# PulseInOut.net
KiCad netlist of a schematic drawn in EAGLE
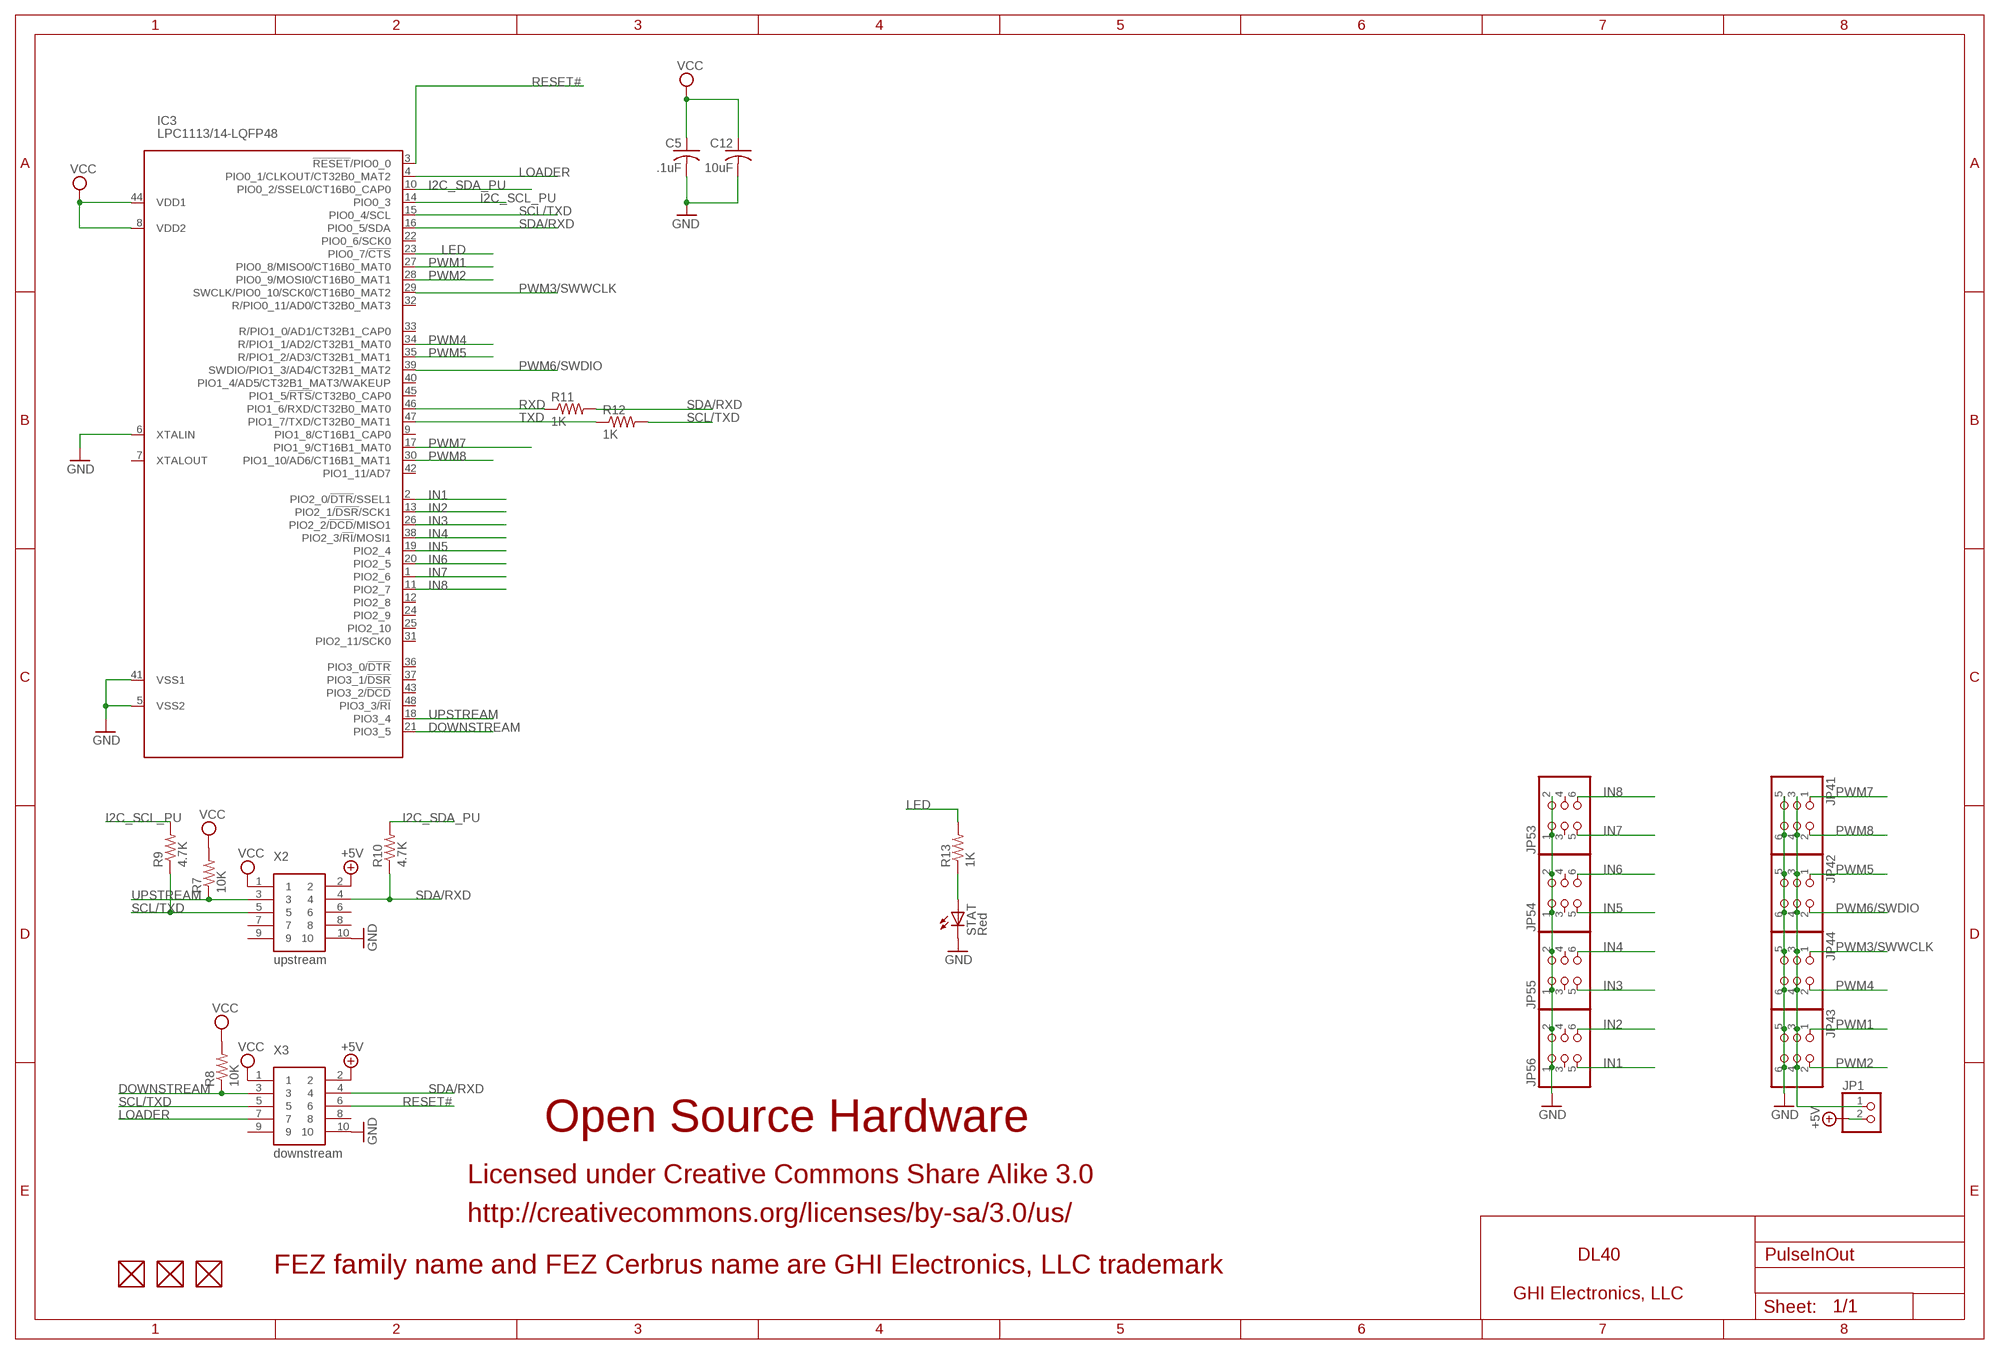
[diagram p0: schematic, sheet 1]

(export (version "E")
  (design (tool "Eeschema 10.0.6"))
  (components
    (comp (ref "C5")
      (value ".1uF")
      (footprint "eagle-import:C0603K")
      (libsource (lib "eagle-import") (part "C-USC0603K"))
    )
    (comp (ref "C12")
      (value "10uF")
      (footprint "eagle-import:C0805K")
      (libsource (lib "eagle-import") (part "C-USC0805K"))
    )
    (comp (ref "FUD4")
      (value "FIDUCIAL")
      (footprint "eagle-import:FIDUCIAL_40MIL")
      (libsource (lib "eagle-import") (part "FIDUCIAL"))
    )
    (comp (ref "FUD5")
      (value "FIDUCIAL")
      (footprint "eagle-import:FIDUCIAL_40MIL")
      (libsource (lib "eagle-import") (part "FIDUCIAL"))
    )
    (comp (ref "FUD6")
      (value "FIDUCIAL")
      (footprint "eagle-import:FIDUCIAL_40MIL")
      (libsource (lib "eagle-import") (part "FIDUCIAL"))
    )
    (comp (ref "IC3")
      (value "LPC1113/14-LQFP48")
      (footprint "eagle-import:LQFP48")
      (libsource (lib "eagle-import") (part "LPC1113/14-LQFP48"))
    )
    (comp (ref "JP1")
      (value "PINHD-1X2")
      (footprint "eagle-import:1X02")
      (libsource (lib "eagle-import") (part "PINHD-1X2"))
    )
    (comp (ref "JP41")
      (value "PINHD-2X3")
      (footprint "eagle-import:2X03")
      (libsource (lib "eagle-import") (part "PINHD-2X3"))
    )
    (comp (ref "JP42")
      (value "PINHD-2X3")
      (footprint "eagle-import:2X03")
      (libsource (lib "eagle-import") (part "PINHD-2X3"))
    )
    (comp (ref "JP43")
      (value "PINHD-2X3")
      (footprint "eagle-import:2X03")
      (libsource (lib "eagle-import") (part "PINHD-2X3"))
    )
    (comp (ref "JP44")
      (value "PINHD-2X3")
      (footprint "eagle-import:2X03")
      (libsource (lib "eagle-import") (part "PINHD-2X3"))
    )
    (comp (ref "JP53")
      (value "PINHD-2X3")
      (footprint "eagle-import:2X03")
      (libsource (lib "eagle-import") (part "PINHD-2X3"))
    )
    (comp (ref "JP54")
      (value "PINHD-2X3")
      (footprint "eagle-import:2X03")
      (libsource (lib "eagle-import") (part "PINHD-2X3"))
    )
    (comp (ref "JP55")
      (value "PINHD-2X3")
      (footprint "eagle-import:2X03")
      (libsource (lib "eagle-import") (part "PINHD-2X3"))
    )
    (comp (ref "JP56")
      (value "PINHD-2X3")
      (footprint "eagle-import:2X03")
      (libsource (lib "eagle-import") (part "PINHD-2X3"))
    )
    (comp (ref "R7")
      (value "10K")
      (footprint "eagle-import:R0603")
      (libsource (lib "eagle-import") (part "R-US_R0603"))
    )
    (comp (ref "R8")
      (value "10K")
      (footprint "eagle-import:R0603")
      (libsource (lib "eagle-import") (part "R-US_R0603"))
    )
    (comp (ref "R9")
      (value "4.7K")
      (footprint "eagle-import:R0603")
      (libsource (lib "eagle-import") (part "R-US_R0603"))
    )
    (comp (ref "R10")
      (value "4.7K")
      (footprint "eagle-import:R0603")
      (libsource (lib "eagle-import") (part "R-US_R0603"))
    )
    (comp (ref "R11")
      (value "1K")
      (footprint "eagle-import:R0603")
      (libsource (lib "eagle-import") (part "R-US_R0603"))
    )
    (comp (ref "R12")
      (value "1K")
      (footprint "eagle-import:R0603")
      (libsource (lib "eagle-import") (part "R-US_R0603"))
    )
    (comp (ref "R13")
      (value "1K")
      (footprint "eagle-import:R0603")
      (libsource (lib "eagle-import") (part "R-US_R0603"))
    )
    (comp (ref "STAT")
      (value "Red")
      (footprint "eagle-import:CHIPLED_0805")
      (libsource (lib "eagle-import") (part "LEDCHIPLED_0805"))
    )
    (comp (ref "X2")
      (value "upstream")
      (footprint "eagle-import:2X5_1.27MM")
      (libsource (lib "eagle-import") (part "2X5_1.27MM"))
    )
    (comp (ref "X3")
      (value "downstream")
      (footprint "eagle-import:2X5_1.27MM")
      (libsource (lib "eagle-import") (part "2X5_1.27MM"))
    )
  )
  (nets
    (net (code "1") (name "+5V") (class "Default")
      (node (ref "JP1") (pin "2") (pinfunction "2_2") (pintype "passive"))
      (node (ref "X2") (pin "2") (pinfunction "2_2") (pintype "bidirectional"))
      (node (ref "X3") (pin "2") (pinfunction "2_2") (pintype "bidirectional"))
    )
    (net (code "2") (name "/DOWNSTREAM") (class "Default")
      (node (ref "IC3") (pin "21") (pinfunction "PIO3_5_21") (pintype "bidirectional"))
      (node (ref "R8") (pin "1") (pinfunction "1_1") (pintype "passive"))
      (node (ref "X3") (pin "3") (pinfunction "3_3") (pintype "bidirectional"))
    )
    (net (code "3") (name "/I2C_SCL_PU") (class "Default")
      (node (ref "IC3") (pin "14") (pinfunction "PIO0_3_14") (pintype "bidirectional"))
      (node (ref "R9") (pin "2") (pinfunction "2_2") (pintype "passive"))
    )
    (net (code "4") (name "/I2C_SDA_PU") (class "Default")
      (node (ref "IC3") (pin "10") (pinfunction "PIO0_2/SSEL0/CT16B0_CAP0_10") (pintype "bidirectional"))
      (node (ref "R10") (pin "2") (pinfunction "2_2") (pintype "passive"))
    )
    (net (code "5") (name "/IN1") (class "Default")
      (node (ref "IC3") (pin "2") (pinfunction "PIO2_0/~{DTR}/SSEL1_2") (pintype "bidirectional"))
      (node (ref "JP56") (pin "5") (pinfunction "5_5") (pintype "passive"))
    )
    (net (code "6") (name "/IN2") (class "Default")
      (node (ref "IC3") (pin "13") (pinfunction "PIO2_1/~{DSR}/SCK1_13") (pintype "bidirectional"))
      (node (ref "JP56") (pin "6") (pinfunction "6_6") (pintype "passive"))
    )
    (net (code "7") (name "/IN3") (class "Default")
      (node (ref "IC3") (pin "26") (pinfunction "PIO2_2/~{DCD}/MISO1_26") (pintype "bidirectional"))
      (node (ref "JP55") (pin "5") (pinfunction "5_5") (pintype "passive"))
    )
    (net (code "8") (name "/IN4") (class "Default")
      (node (ref "IC3") (pin "38") (pinfunction "PIO2_3/~{RI}/MOSI1_38") (pintype "bidirectional"))
      (node (ref "JP55") (pin "6") (pinfunction "6_6") (pintype "passive"))
    )
    (net (code "9") (name "/IN5") (class "Default")
      (node (ref "IC3") (pin "19") (pinfunction "PIO2_4_19") (pintype "bidirectional"))
      (node (ref "JP54") (pin "5") (pinfunction "5_5") (pintype "passive"))
    )
    (net (code "10") (name "/IN6") (class "Default")
      (node (ref "IC3") (pin "20") (pinfunction "PIO2_5_20") (pintype "bidirectional"))
      (node (ref "JP54") (pin "6") (pinfunction "6_6") (pintype "passive"))
    )
    (net (code "11") (name "/IN7") (class "Default")
      (node (ref "IC3") (pin "1") (pinfunction "PIO2_6_1") (pintype "bidirectional"))
      (node (ref "JP53") (pin "5") (pinfunction "5_5") (pintype "passive"))
    )
    (net (code "12") (name "/IN8") (class "Default")
      (node (ref "IC3") (pin "11") (pinfunction "PIO2_7_11") (pintype "bidirectional"))
      (node (ref "JP53") (pin "6") (pinfunction "6_6") (pintype "passive"))
    )
    (net (code "13") (name "/LED") (class "Default")
      (node (ref "IC3") (pin "23") (pinfunction "PIO0_7/~{CTS}_23") (pintype "bidirectional"))
      (node (ref "R13") (pin "2") (pinfunction "2_2") (pintype "passive"))
    )
    (net (code "14") (name "/LOADER") (class "Default")
      (node (ref "IC3") (pin "4") (pinfunction "PIO0_1/CLKOUT/CT32B0_MAT2_4") (pintype "bidirectional"))
      (node (ref "X3") (pin "7") (pinfunction "7_7") (pintype "bidirectional"))
    )
    (net (code "15") (name "/PWM1") (class "Default")
      (node (ref "IC3") (pin "27") (pinfunction "PIO0_8/MISO0/CT16B0_MAT0_27") (pintype "bidirectional"))
      (node (ref "JP43") (pin "1") (pinfunction "1_1") (pintype "passive"))
    )
    (net (code "16") (name "/PWM2") (class "Default")
      (node (ref "IC3") (pin "28") (pinfunction "PIO0_9/MOSI0/CT16B0_MAT1_28") (pintype "bidirectional"))
      (node (ref "JP43") (pin "2") (pinfunction "2_2") (pintype "passive"))
    )
    (net (code "17") (name "/PWM3{slash}SWWCLK") (class "Default")
      (node (ref "IC3") (pin "29") (pinfunction "SWCLK/PIO0_10/SCK0/CT16B0_MAT2_29") (pintype "bidirectional"))
      (node (ref "JP44") (pin "1") (pinfunction "1_1") (pintype "passive"))
    )
    (net (code "18") (name "/PWM4") (class "Default")
      (node (ref "IC3") (pin "34") (pinfunction "R/PIO1_1/AD2/CT32B1_MAT0_34") (pintype "bidirectional"))
      (node (ref "JP44") (pin "2") (pinfunction "2_2") (pintype "passive"))
    )
    (net (code "19") (name "/PWM5") (class "Default")
      (node (ref "IC3") (pin "35") (pinfunction "R/PIO1_2/AD3/CT32B1_MAT1_35") (pintype "bidirectional"))
      (node (ref "JP42") (pin "1") (pinfunction "1_1") (pintype "passive"))
    )
    (net (code "20") (name "/PWM6{slash}SWDIO") (class "Default")
      (node (ref "IC3") (pin "39") (pinfunction "SWDIO/PIO1_3/AD4/CT32B1_MAT2_39") (pintype "bidirectional"))
      (node (ref "JP42") (pin "2") (pinfunction "2_2") (pintype "passive"))
    )
    (net (code "21") (name "/PWM7") (class "Default")
      (node (ref "IC3") (pin "17") (pinfunction "PIO1_9/CT16B1_MAT0_17") (pintype "bidirectional"))
      (node (ref "JP41") (pin "1") (pinfunction "1_1") (pintype "passive"))
    )
    (net (code "22") (name "/PWM8") (class "Default")
      (node (ref "IC3") (pin "30") (pinfunction "PIO1_10/AD6/CT16B1_MAT1_30") (pintype "bidirectional"))
      (node (ref "JP41") (pin "2") (pinfunction "2_2") (pintype "passive"))
    )
    (net (code "23") (name "/RESET#") (class "Default")
      (node (ref "IC3") (pin "3") (pinfunction "~{RESET}/PIO0_0_3") (pintype "bidirectional"))
      (node (ref "X3") (pin "6") (pinfunction "6_6") (pintype "bidirectional"))
    )
    (net (code "24") (name "/RXD") (class "Default")
      (node (ref "IC3") (pin "46") (pinfunction "PIO1_6/RXD/CT32B0_MAT0_46") (pintype "bidirectional"))
      (node (ref "R11") (pin "1") (pinfunction "1_1") (pintype "passive"))
    )
    (net (code "25") (name "/SCL{slash}TXD") (class "Default")
      (node (ref "IC3") (pin "15") (pinfunction "PIO0_4/SCL_15") (pintype "bidirectional"))
      (node (ref "R12") (pin "2") (pinfunction "2_2") (pintype "passive"))
      (node (ref "R9") (pin "1") (pinfunction "1_1") (pintype "passive"))
      (node (ref "X2") (pin "5") (pinfunction "5_5") (pintype "bidirectional"))
      (node (ref "X3") (pin "5") (pinfunction "5_5") (pintype "bidirectional"))
    )
    (net (code "26") (name "/SDA{slash}RXD") (class "Default")
      (node (ref "IC3") (pin "16") (pinfunction "PIO0_5/SDA_16") (pintype "bidirectional"))
      (node (ref "R10") (pin "1") (pinfunction "1_1") (pintype "passive"))
      (node (ref "R11") (pin "2") (pinfunction "2_2") (pintype "passive"))
      (node (ref "X2") (pin "4") (pinfunction "4_4") (pintype "bidirectional"))
      (node (ref "X3") (pin "4") (pinfunction "4_4") (pintype "bidirectional"))
    )
    (net (code "27") (name "/TXD") (class "Default")
      (node (ref "IC3") (pin "47") (pinfunction "PIO1_7/TXD/CT32B0_MAT1_47") (pintype "bidirectional"))
      (node (ref "R12") (pin "1") (pinfunction "1_1") (pintype "passive"))
    )
    (net (code "28") (name "/UPSTREAM") (class "Default")
      (node (ref "IC3") (pin "18") (pinfunction "PIO3_4_18") (pintype "bidirectional"))
      (node (ref "R7") (pin "1") (pinfunction "1_1") (pintype "passive"))
      (node (ref "X2") (pin "3") (pinfunction "3_3") (pintype "bidirectional"))
    )
    (net (code "29") (name "GND") (class "Default")
      (node (ref "C12") (pin "2") (pinfunction "2_2") (pintype "passive"))
      (node (ref "C5") (pin "2") (pinfunction "2_2") (pintype "passive"))
      (node (ref "IC3") (pin "41") (pinfunction "VSS1_41") (pintype "power_in"))
      (node (ref "IC3") (pin "5") (pinfunction "VSS2_5") (pintype "power_in"))
      (node (ref "IC3") (pin "6") (pinfunction "XTALIN_6") (pintype "passive"))
      (node (ref "JP41") (pin "5") (pinfunction "5_5") (pintype "passive"))
      (node (ref "JP41") (pin "6") (pinfunction "6_6") (pintype "passive"))
      (node (ref "JP42") (pin "5") (pinfunction "5_5") (pintype "passive"))
      (node (ref "JP42") (pin "6") (pinfunction "6_6") (pintype "passive"))
      (node (ref "JP43") (pin "5") (pinfunction "5_5") (pintype "passive"))
      (node (ref "JP43") (pin "6") (pinfunction "6_6") (pintype "passive"))
      (node (ref "JP44") (pin "5") (pinfunction "5_5") (pintype "passive"))
      (node (ref "JP44") (pin "6") (pinfunction "6_6") (pintype "passive"))
      (node (ref "JP53") (pin "1") (pinfunction "1_1") (pintype "passive"))
      (node (ref "JP53") (pin "2") (pinfunction "2_2") (pintype "passive"))
      (node (ref "JP54") (pin "1") (pinfunction "1_1") (pintype "passive"))
      (node (ref "JP54") (pin "2") (pinfunction "2_2") (pintype "passive"))
      (node (ref "JP55") (pin "1") (pinfunction "1_1") (pintype "passive"))
      (node (ref "JP55") (pin "2") (pinfunction "2_2") (pintype "passive"))
      (node (ref "JP56") (pin "1") (pinfunction "1_1") (pintype "passive"))
      (node (ref "JP56") (pin "2") (pinfunction "2_2") (pintype "passive"))
      (node (ref "STAT") (pin "C") (pinfunction "C_C") (pintype "passive"))
      (node (ref "X2") (pin "10") (pinfunction "10_10") (pintype "bidirectional"))
      (node (ref "X3") (pin "10") (pinfunction "10_10") (pintype "bidirectional"))
    )
    (net (code "30") (name "Net-(JP1-Pad1)") (class "Default")
      (node (ref "JP1") (pin "1") (pinfunction "1_1") (pintype "passive"))
      (node (ref "JP41") (pin "3") (pinfunction "3_3") (pintype "passive"))
      (node (ref "JP41") (pin "4") (pinfunction "4_4") (pintype "passive"))
      (node (ref "JP42") (pin "3") (pinfunction "3_3") (pintype "passive"))
      (node (ref "JP42") (pin "4") (pinfunction "4_4") (pintype "passive"))
      (node (ref "JP43") (pin "3") (pinfunction "3_3") (pintype "passive"))
      (node (ref "JP43") (pin "4") (pinfunction "4_4") (pintype "passive"))
      (node (ref "JP44") (pin "3") (pinfunction "3_3") (pintype "passive"))
      (node (ref "JP44") (pin "4") (pinfunction "4_4") (pintype "passive"))
    )
    (net (code "31") (name "Net-(R13-Pad1)") (class "Default")
      (node (ref "R13") (pin "1") (pinfunction "1_1") (pintype "passive"))
      (node (ref "STAT") (pin "A") (pinfunction "A_A") (pintype "passive"))
    )
    (net (code "32") (name "VCC") (class "Default")
      (node (ref "C12") (pin "1") (pinfunction "1_1") (pintype "passive"))
      (node (ref "C5") (pin "1") (pinfunction "1_1") (pintype "passive"))
      (node (ref "IC3") (pin "44") (pinfunction "VDD1_44") (pintype "power_in"))
      (node (ref "IC3") (pin "8") (pinfunction "VDD2_8") (pintype "power_in"))
      (node (ref "R7") (pin "2") (pinfunction "2_2") (pintype "passive"))
      (node (ref "R8") (pin "2") (pinfunction "2_2") (pintype "passive"))
      (node (ref "X2") (pin "1") (pinfunction "1_1") (pintype "bidirectional"))
      (node (ref "X3") (pin "1") (pinfunction "1_1") (pintype "bidirectional"))
    )
    (net (code "33") (name "unconnected-(FUD4-PadP$1)") (class "Default")
      (node (ref "FUD4") (pin "P$1") (pinfunction "P$1_P$1") (pintype "no_connect"))
    )
    (net (code "34") (name "unconnected-(FUD5-PadP$1)") (class "Default")
      (node (ref "FUD5") (pin "P$1") (pinfunction "P$1_P$1") (pintype "no_connect"))
    )
    (net (code "35") (name "unconnected-(FUD6-PadP$1)") (class "Default")
      (node (ref "FUD6") (pin "P$1") (pinfunction "P$1_P$1") (pintype "no_connect"))
    )
    (net (code "36") (name "unconnected-(IC3-PIO0_6{slash}SCK0-Pad22)") (class "Default")
      (node (ref "IC3") (pin "22") (pinfunction "PIO0_6/SCK0_22") (pintype "bidirectional"))
    )
    (net (code "37") (name "unconnected-(IC3-PIO1_4{slash}AD5{slash}CT32B1_MAT3{slash}WAKEUP-Pad40)") (class "Default")
      (node (ref "IC3") (pin "40") (pinfunction "PIO1_4/AD5/CT32B1_MAT3/WAKEUP_40") (pintype "bidirectional"))
    )
    (net (code "38") (name "unconnected-(IC3-PIO1_5{slash}~{RTS}{slash}CT32B0_CAP0-Pad45)") (class "Default")
      (node (ref "IC3") (pin "45") (pinfunction "PIO1_5/~{RTS}/CT32B0_CAP0_45") (pintype "bidirectional"))
    )
    (net (code "39") (name "unconnected-(IC3-PIO1_8{slash}CT16B1_CAP0-Pad9)") (class "Default")
      (node (ref "IC3") (pin "9") (pinfunction "PIO1_8/CT16B1_CAP0_9") (pintype "bidirectional"))
    )
    (net (code "40") (name "unconnected-(IC3-PIO1_11{slash}AD7-Pad42)") (class "Default")
      (node (ref "IC3") (pin "42") (pinfunction "PIO1_11/AD7_42") (pintype "bidirectional"))
    )
    (net (code "41") (name "unconnected-(IC3-PIO2_8-Pad12)") (class "Default")
      (node (ref "IC3") (pin "12") (pinfunction "PIO2_8_12") (pintype "bidirectional"))
    )
    (net (code "42") (name "unconnected-(IC3-PIO2_9-Pad24)") (class "Default")
      (node (ref "IC3") (pin "24") (pinfunction "PIO2_9_24") (pintype "bidirectional"))
    )
    (net (code "43") (name "unconnected-(IC3-PIO2_10-Pad25)") (class "Default")
      (node (ref "IC3") (pin "25") (pinfunction "PIO2_10_25") (pintype "bidirectional"))
    )
    (net (code "44") (name "unconnected-(IC3-PIO2_11{slash}SCK0-Pad31)") (class "Default")
      (node (ref "IC3") (pin "31") (pinfunction "PIO2_11/SCK0_31") (pintype "bidirectional"))
    )
    (net (code "45") (name "unconnected-(IC3-PIO3_0{slash}~{DTR}-Pad36)") (class "Default")
      (node (ref "IC3") (pin "36") (pinfunction "PIO3_0/~{DTR}_36") (pintype "bidirectional"))
    )
    (net (code "46") (name "unconnected-(IC3-PIO3_1{slash}~{DSR}-Pad37)") (class "Default")
      (node (ref "IC3") (pin "37") (pinfunction "PIO3_1/~{DSR}_37") (pintype "bidirectional"))
    )
    (net (code "47") (name "unconnected-(IC3-PIO3_2{slash}~{DCD}-Pad43)") (class "Default")
      (node (ref "IC3") (pin "43") (pinfunction "PIO3_2/~{DCD}_43") (pintype "bidirectional"))
    )
    (net (code "48") (name "unconnected-(IC3-PIO3_3{slash}~{RI}-Pad48)") (class "Default")
      (node (ref "IC3") (pin "48") (pinfunction "PIO3_3/~{RI}_48") (pintype "bidirectional"))
    )
    (net (code "49") (name "unconnected-(IC3-R{slash}PIO0_11{slash}AD0{slash}CT32B0_MAT3-Pad32)") (class "Default")
      (node (ref "IC3") (pin "32") (pinfunction "R/PIO0_11/AD0/CT32B0_MAT3_32") (pintype "bidirectional"))
    )
    (net (code "50") (name "unconnected-(IC3-R{slash}PIO1_0{slash}AD1{slash}CT32B1_CAP0-Pad33)") (class "Default")
      (node (ref "IC3") (pin "33") (pinfunction "R/PIO1_0/AD1/CT32B1_CAP0_33") (pintype "bidirectional"))
    )
    (net (code "51") (name "unconnected-(IC3-XTALOUT-Pad7)") (class "Default")
      (node (ref "IC3") (pin "7") (pinfunction "XTALOUT_7") (pintype "passive"))
    )
    (net (code "52") (name "unconnected-(JP53-Pad3)") (class "Default")
      (node (ref "JP53") (pin "3") (pinfunction "3_3") (pintype "passive"))
    )
    (net (code "53") (name "unconnected-(JP53-Pad4)") (class "Default")
      (node (ref "JP53") (pin "4") (pinfunction "4_4") (pintype "passive"))
    )
    (net (code "54") (name "unconnected-(JP54-Pad3)") (class "Default")
      (node (ref "JP54") (pin "3") (pinfunction "3_3") (pintype "passive"))
    )
    (net (code "55") (name "unconnected-(JP54-Pad4)") (class "Default")
      (node (ref "JP54") (pin "4") (pinfunction "4_4") (pintype "passive"))
    )
    (net (code "56") (name "unconnected-(JP55-Pad3)") (class "Default")
      (node (ref "JP55") (pin "3") (pinfunction "3_3") (pintype "passive"))
    )
    (net (code "57") (name "unconnected-(JP55-Pad4)") (class "Default")
      (node (ref "JP55") (pin "4") (pinfunction "4_4") (pintype "passive"))
    )
    (net (code "58") (name "unconnected-(JP56-Pad3)") (class "Default")
      (node (ref "JP56") (pin "3") (pinfunction "3_3") (pintype "passive"))
    )
    (net (code "59") (name "unconnected-(JP56-Pad4)") (class "Default")
      (node (ref "JP56") (pin "4") (pinfunction "4_4") (pintype "passive"))
    )
    (net (code "60") (name "unconnected-(X2-Pad6)") (class "Default")
      (node (ref "X2") (pin "6") (pinfunction "6_6") (pintype "bidirectional"))
    )
    (net (code "61") (name "unconnected-(X2-Pad7)") (class "Default")
      (node (ref "X2") (pin "7") (pinfunction "7_7") (pintype "bidirectional"))
    )
    (net (code "62") (name "unconnected-(X2-Pad8)") (class "Default")
      (node (ref "X2") (pin "8") (pinfunction "8_8") (pintype "bidirectional"))
    )
    (net (code "63") (name "unconnected-(X2-Pad9)") (class "Default")
      (node (ref "X2") (pin "9") (pinfunction "9_9") (pintype "bidirectional"))
    )
    (net (code "64") (name "unconnected-(X3-Pad8)") (class "Default")
      (node (ref "X3") (pin "8") (pinfunction "8_8") (pintype "bidirectional"))
    )
    (net (code "65") (name "unconnected-(X3-Pad9)") (class "Default")
      (node (ref "X3") (pin "9") (pinfunction "9_9") (pintype "bidirectional"))
    )
  )
)
